# Touch.net
KiCad netlist of a schematic drawn in Altium Designer
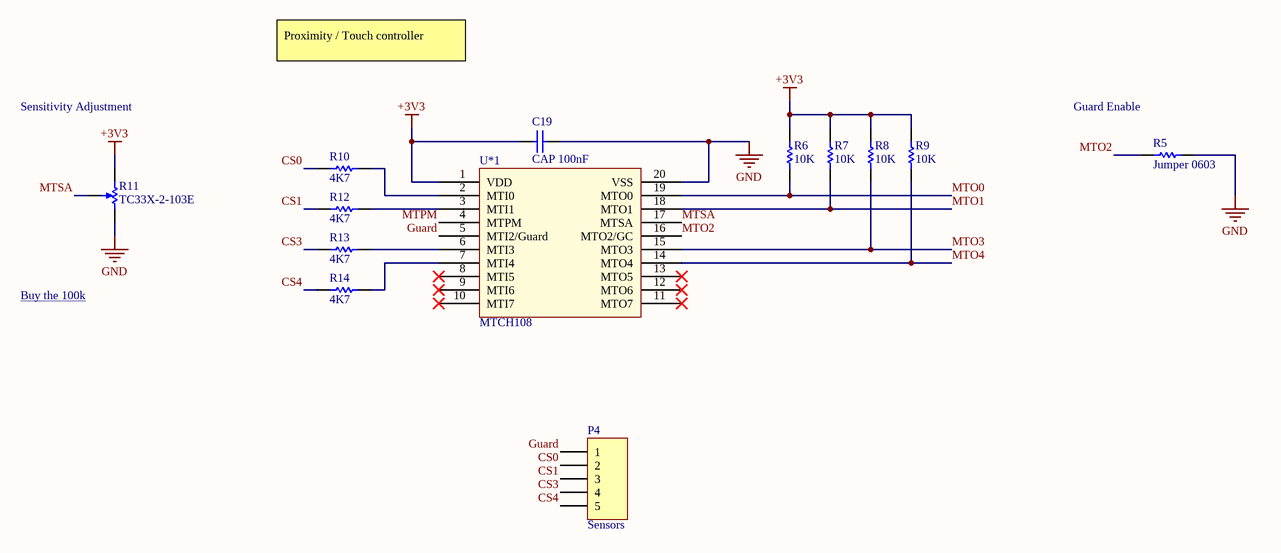
[diagram p0: Touch.SchDoc]

(export (version "E")
  (design (tool "Eeschema 10.0.6"))
  (components
    (comp (ref "C19")
      (value "CAP 100nF")
      (footprint "CAPC0603(1608)100_M")
      (description "CAP 100nF 16V ±5% 0603 (1608 Metric) Thickness 1mm SMD")
      (fields (field (name "TOLERANCE") "Â±5%"))
      (libsource (lib "Altium Content Vault") (part "CAP"))
    )
    (comp (ref "P4")
      (value "Sensors")
      (footprint "HDR1X5")
      (description "Header, 5-Pin")
      (fields (field (name "PUBLISHER") "Altium Limited"))
      (libsource (lib "Miscellaneous Connectors") (part "Header 5"))
    )
    (comp (ref "R5")
      (value "Jumper 0603")
      (footprint "RESC0603(1608)_N")
      (description "Jumper 0603 (1608 Metric)")
      (fields (field (name "POWER") "None"))
      (libsource (lib "Altium Content Vault") (part "RES"))
    )
    (comp (ref "R6")
      (value "10K")
      (footprint "RESC0603(1608)_N")
      (description "10K 0.1W 5% 0603 (1608 Metric)  SMD")
      (fields (field (name "TOLERANCE") "5 %") (field (name "POWER") "0.1 W"))
      (libsource (lib "Altium Content Vault") (part "RES"))
    )
    (comp (ref "R7")
      (value "10K")
      (footprint "RESC0603(1608)_N")
      (description "10K 0.1W 5% 0603 (1608 Metric)  SMD")
      (fields (field (name "TOLERANCE") "5 %") (field (name "POWER") "0.1 W"))
      (libsource (lib "Altium Content Vault") (part "RES"))
    )
    (comp (ref "R8")
      (value "10K")
      (footprint "RESC0603(1608)_N")
      (description "10K 0.1W 5% 0603 (1608 Metric)  SMD")
      (fields (field (name "TOLERANCE") "5 %") (field (name "POWER") "0.1 W"))
      (libsource (lib "Altium Content Vault") (part "RES"))
    )
    (comp (ref "R9")
      (value "10K")
      (footprint "RESC0603(1608)_N")
      (description "10K 0.1W 5% 0603 (1608 Metric)  SMD")
      (fields (field (name "TOLERANCE") "5 %") (field (name "POWER") "0.1 W"))
      (libsource (lib "Altium Content Vault") (part "RES"))
    )
    (comp (ref "R10")
      (value "4K7")
      (footprint "RESC0603(1608)_N")
      (description "4K7 0.1W 5% 0603 (1608 Metric)  SMD")
      (fields (field (name "TOLERANCE") "5 %") (field (name "POWER") "0.1 W"))
      (libsource (lib "Altium Content Vault") (part "RES"))
    )
    (comp (ref "R11")
      (value "TC33X-2-103E")
      (footprint "BOUR-TC33X-2_V")
      (description "Trimming Potentiometer, 10000 Ohm, -40 to 100 degC, 3-Pin SMD, RoHS, Tape and Reel")
      (fields (field (name "TOLERANCE") "25%") (field (name "MANUFACTURER") "Bourns"))
      (libsource (lib "Altium Content Vault") (part "RES-ADJ-3_A"))
    )
    (comp (ref "R12")
      (value "4K7")
      (footprint "RESC0603(1608)_N")
      (description "4K7 0.1W 5% 0603 (1608 Metric)  SMD")
      (fields (field (name "TOLERANCE") "5 %") (field (name "POWER") "0.1 W"))
      (libsource (lib "Altium Content Vault") (part "RES"))
    )
    (comp (ref "R13")
      (value "4K7")
      (footprint "RESC0603(1608)_N")
      (description "4K7 0.1W 5% 0603 (1608 Metric)  SMD")
      (fields (field (name "TOLERANCE") "5 %") (field (name "POWER") "0.1 W"))
      (libsource (lib "Altium Content Vault") (part "RES"))
    )
    (comp (ref "R14")
      (value "4K7")
      (footprint "RESC0603(1608)_N")
      (description "4K7 0.1W 5% 0603 (1608 Metric)  SMD")
      (fields (field (name "TOLERANCE") "5 %") (field (name "POWER") "0.1 W"))
      (libsource (lib "Altium Content Vault") (part "RES"))
    )
    (comp (ref "U*1")
      (value "MTCH108")
      (footprint "MTCH-108 SSOP")
      (libsource (lib "LED_Nixie_Display") (part "MTCH108"))
    )
  )
  (nets
    (net (code "1") (name "+3V3") (class "Default")
      (node (ref "C19") (pin "2") (pinfunction "2_2") (pintype "passive"))
      (node (ref "R11") (pin "1") (pinfunction "1_1") (pintype "passive"))
      (node (ref "R6") (pin "2") (pinfunction "2_2") (pintype "passive"))
      (node (ref "R7") (pin "2") (pinfunction "2_2") (pintype "passive"))
      (node (ref "R8") (pin "2") (pinfunction "2_2") (pintype "passive"))
      (node (ref "R9") (pin "2") (pinfunction "2_2") (pintype "passive"))
      (node (ref "U*1") (pin "1") (pinfunction "VDD_1") (pintype "passive"))
    )
    (net (code "2") (name "/CS0") (class "Default")
      (node (ref "P4") (pin "2") (pinfunction "2_2") (pintype "passive"))
      (node (ref "R10") (pin "1") (pinfunction "1_1") (pintype "passive"))
    )
    (net (code "3") (name "/CS1") (class "Default")
      (node (ref "P4") (pin "3") (pinfunction "3_3") (pintype "passive"))
      (node (ref "R12") (pin "1") (pinfunction "1_1") (pintype "passive"))
    )
    (net (code "4") (name "/CS3") (class "Default")
      (node (ref "P4") (pin "4") (pinfunction "4_4") (pintype "passive"))
      (node (ref "R13") (pin "1") (pinfunction "1_1") (pintype "passive"))
    )
    (net (code "5") (name "/CS4") (class "Default")
      (node (ref "P4") (pin "5") (pinfunction "5_5") (pintype "passive"))
      (node (ref "R14") (pin "1") (pinfunction "1_1") (pintype "passive"))
    )
    (net (code "6") (name "/Guard") (class "Default")
      (node (ref "P4") (pin "1") (pinfunction "1_1") (pintype "passive"))
      (node (ref "U*1") (pin "5") (pinfunction "MTI2/Guard_5") (pintype "passive"))
    )
    (net (code "7") (name "/MTO0") (class "Default")
      (node (ref "R6") (pin "1") (pinfunction "1_1") (pintype "passive"))
      (node (ref "U*1") (pin "19") (pinfunction "MTO0_19") (pintype "passive"))
    )
    (net (code "8") (name "/MTO1") (class "Default")
      (node (ref "R7") (pin "1") (pinfunction "1_1") (pintype "passive"))
      (node (ref "U*1") (pin "18") (pinfunction "MTO1_18") (pintype "passive"))
    )
    (net (code "9") (name "/MTO2") (class "Default")
      (node (ref "R5") (pin "1") (pinfunction "1_1") (pintype "passive"))
      (node (ref "U*1") (pin "16") (pinfunction "MTO2/GC_16") (pintype "passive"))
    )
    (net (code "10") (name "/MTO3") (class "Default")
      (node (ref "R8") (pin "1") (pinfunction "1_1") (pintype "passive"))
      (node (ref "U*1") (pin "15") (pinfunction "MTO3_15") (pintype "passive"))
    )
    (net (code "11") (name "/MTO4") (class "Default")
      (node (ref "R9") (pin "1") (pinfunction "1_1") (pintype "passive"))
      (node (ref "U*1") (pin "14") (pinfunction "MTO4_14") (pintype "passive"))
    )
    (net (code "12") (name "/MTPM") (class "Default")
      (node (ref "U*1") (pin "4") (pinfunction "MTPM_4") (pintype "passive"))
    )
    (net (code "13") (name "/MTSA") (class "Default")
      (node (ref "R11") (pin "2") (pinfunction "2_2") (pintype "passive"))
      (node (ref "U*1") (pin "17") (pinfunction "MTSA_17") (pintype "passive"))
    )
    (net (code "14") (name "GND") (class "Default")
      (node (ref "C19") (pin "1") (pinfunction "1_1") (pintype "passive"))
      (node (ref "R11") (pin "3") (pinfunction "3_3") (pintype "passive"))
      (node (ref "R5") (pin "2") (pinfunction "2_2") (pintype "passive"))
      (node (ref "U*1") (pin "20") (pinfunction "VSS_20") (pintype "passive"))
    )
    (net (code "15") (name "Net-(U*1-MTI0)") (class "Default")
      (node (ref "R10") (pin "2") (pinfunction "2_2") (pintype "passive"))
      (node (ref "U*1") (pin "2") (pinfunction "MTI0_2") (pintype "passive"))
    )
    (net (code "16") (name "Net-(U*1-MTI1)") (class "Default")
      (node (ref "R12") (pin "2") (pinfunction "2_2") (pintype "passive"))
      (node (ref "U*1") (pin "3") (pinfunction "MTI1_3") (pintype "passive"))
    )
    (net (code "17") (name "Net-(U*1-MTI3)") (class "Default")
      (node (ref "R13") (pin "2") (pinfunction "2_2") (pintype "passive"))
      (node (ref "U*1") (pin "6") (pinfunction "MTI3_6") (pintype "passive"))
    )
    (net (code "18") (name "Net-(U*1-MTI4)") (class "Default")
      (node (ref "R14") (pin "2") (pinfunction "2_2") (pintype "passive"))
      (node (ref "U*1") (pin "7") (pinfunction "MTI4_7") (pintype "passive"))
    )
    (net (code "19") (name "unconnected-(U*1-MTI5-Pad8)") (class "Default")
      (node (ref "U*1") (pin "8") (pinfunction "MTI5_8") (pintype "passive+no_connect"))
    )
    (net (code "20") (name "unconnected-(U*1-MTI6-Pad9)") (class "Default")
      (node (ref "U*1") (pin "9") (pinfunction "MTI6_9") (pintype "passive+no_connect"))
    )
    (net (code "21") (name "unconnected-(U*1-MTI7-Pad10)") (class "Default")
      (node (ref "U*1") (pin "10") (pinfunction "MTI7_10") (pintype "passive+no_connect"))
    )
    (net (code "22") (name "unconnected-(U*1-MTO5-Pad13)") (class "Default")
      (node (ref "U*1") (pin "13") (pinfunction "MTO5_13") (pintype "passive+no_connect"))
    )
    (net (code "23") (name "unconnected-(U*1-MTO6-Pad12)") (class "Default")
      (node (ref "U*1") (pin "12") (pinfunction "MTO6_12") (pintype "passive+no_connect"))
    )
    (net (code "24") (name "unconnected-(U*1-MTO7-Pad11)") (class "Default")
      (node (ref "U*1") (pin "11") (pinfunction "MTO7_11") (pintype "passive+no_connect"))
    )
  )
)
